# Power_Controller.net
KiCad netlist of a schematic drawn in Altium Designer
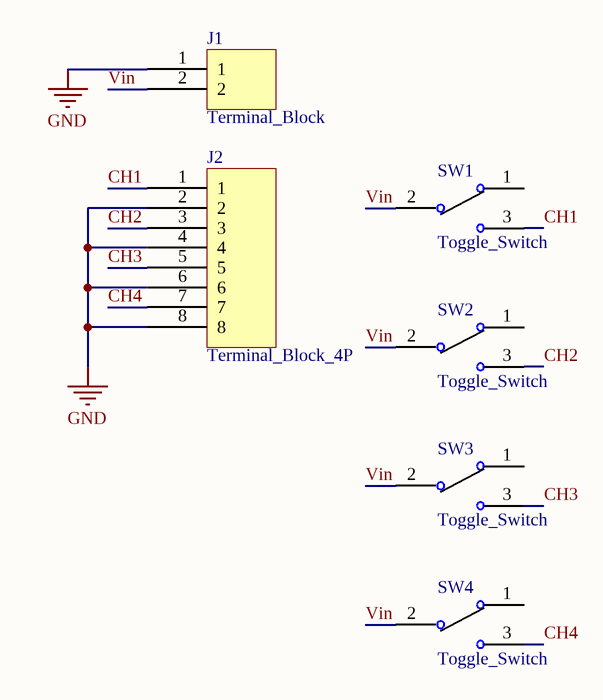
[diagram p0: Power_Controller.SchDoc]

(export (version "E")
  (design (tool "Eeschema 10.0.6"))
  (components
    (comp (ref "J1")
      (value "Terminal_Block")
      (footprint "terminal_block_2P_V2")
      (libsource (lib "Lab_share") (part "Terminal_Block_2P"))
    )
    (comp (ref "J2")
      (value "Terminal_Block_4P")
      (footprint "terminal_block_4P")
      (libsource (lib "Lab_share") (part "Terminal_Block_4P"))
    )
    (comp (ref "SW1")
      (value "Toggle_Switch")
      (footprint "T_Switch_V1")
      (libsource (lib "Lab_share") (part "Switch_T"))
    )
    (comp (ref "SW2")
      (value "Toggle_Switch")
      (footprint "T_Switch_V1")
      (libsource (lib "Lab_share") (part "Switch_T"))
    )
    (comp (ref "SW3")
      (value "Toggle_Switch")
      (footprint "T_Switch_V1")
      (libsource (lib "Lab_share") (part "Switch_T"))
    )
    (comp (ref "SW4")
      (value "Toggle_Switch")
      (footprint "T_Switch_V1")
      (libsource (lib "Lab_share") (part "Switch_T"))
    )
  )
  (nets
    (net (code "1") (name "/CH1") (class "Default")
      (node (ref "J2") (pin "1") (pinfunction "1_1") (pintype "passive"))
      (node (ref "SW1") (pin "3") (pintype "passive"))
    )
    (net (code "2") (name "/CH2") (class "Default")
      (node (ref "J2") (pin "3") (pinfunction "3_3") (pintype "passive"))
      (node (ref "SW2") (pin "3") (pintype "passive"))
    )
    (net (code "3") (name "/CH3") (class "Default")
      (node (ref "J2") (pin "5") (pinfunction "5_5") (pintype "passive"))
      (node (ref "SW3") (pin "3") (pintype "passive"))
    )
    (net (code "4") (name "/CH4") (class "Default")
      (node (ref "J2") (pin "7") (pinfunction "7_7") (pintype "passive"))
      (node (ref "SW4") (pin "3") (pintype "passive"))
    )
    (net (code "5") (name "/Vin") (class "Default")
      (node (ref "J1") (pin "2") (pinfunction "2_2") (pintype "passive"))
      (node (ref "SW1") (pin "2") (pintype "passive"))
      (node (ref "SW2") (pin "2") (pintype "passive"))
      (node (ref "SW3") (pin "2") (pintype "passive"))
      (node (ref "SW4") (pin "2") (pintype "passive"))
    )
    (net (code "6") (name "GND") (class "Default")
      (node (ref "J1") (pin "1") (pinfunction "1_1") (pintype "passive"))
      (node (ref "J2") (pin "2") (pinfunction "2_2") (pintype "passive"))
      (node (ref "J2") (pin "4") (pinfunction "4_4") (pintype "passive"))
      (node (ref "J2") (pin "6") (pinfunction "6_6") (pintype "passive"))
      (node (ref "J2") (pin "8") (pinfunction "8_8") (pintype "passive"))
    )
    (net (code "7") (name "unconnected-(SW1-Pad1)") (class "Default")
      (node (ref "SW1") (pin "1") (pintype "passive"))
    )
    (net (code "8") (name "unconnected-(SW2-Pad1)") (class "Default")
      (node (ref "SW2") (pin "1") (pintype "passive"))
    )
    (net (code "9") (name "unconnected-(SW3-Pad1)") (class "Default")
      (node (ref "SW3") (pin "1") (pintype "passive"))
    )
    (net (code "10") (name "unconnected-(SW4-Pad1)") (class "Default")
      (node (ref "SW4") (pin "1") (pintype "passive"))
    )
  )
)
